# St_Olavs_Alarm_2.net
KiCad netlist of a schematic drawn in Altium Designer
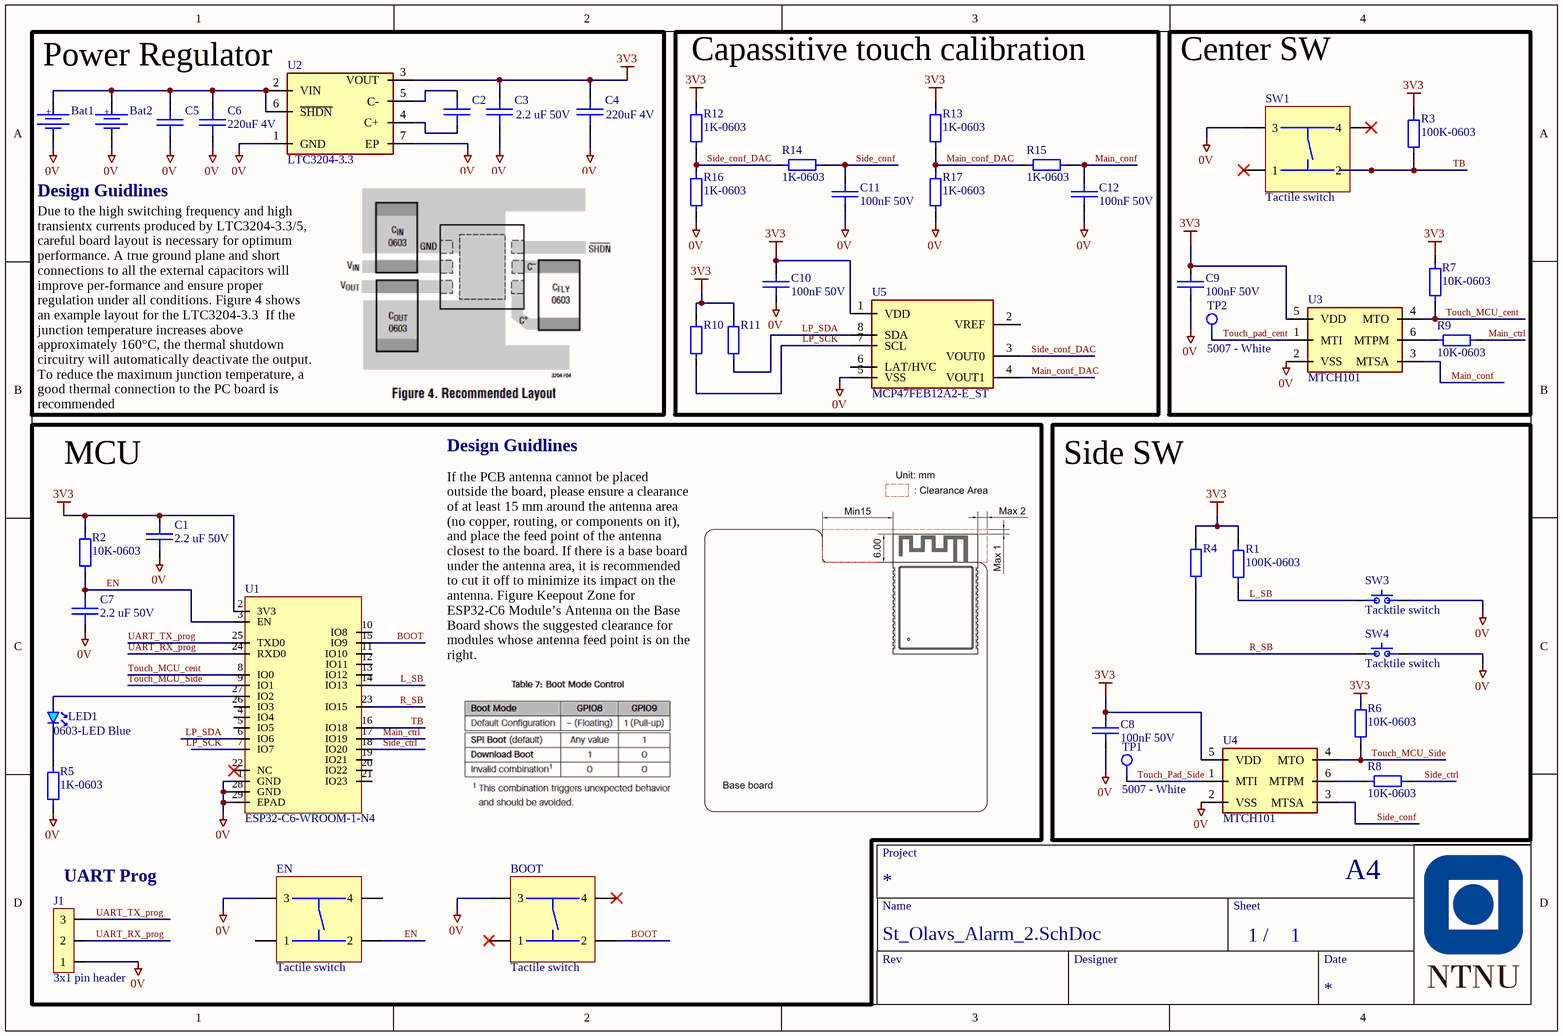
[diagram p0: St_Olavs_Alarm_2.SchDoc]

(export (version "E")
  (design (tool "Eeschema 10.0.6"))
  (components
    (comp (ref "Bat1")
      (value "Bat Holder L-KLS5-CR2032-23-B1")
      (footprint "St_Olavs_alarm:L-KLS5-CR2032-23-B1")
      (description "Bat Holder CR2032 SMD")
      (fields
        (field (name "MANUFACTURER") "KLS Electronic")
        (field (name "MANUFACTURER PART NUMBER") "L-KLS5-CR2032-23-B1")
        (field (name "AUTHOR") "rsk")
      )
      (libsource (lib "St_Olavs_alarm") (part "CMP-023-000003.0.1"))
    )
    (comp (ref "Bat2")
      (value "Bat Holder L-KLS5-CR2032-23-B1")
      (footprint "St_Olavs_alarm:L-KLS5-CR2032-23-B1")
      (description "Bat Holder CR2032 SMD")
      (fields
        (field (name "MANUFACTURER") "KLS Electronic")
        (field (name "MANUFACTURER PART NUMBER") "L-KLS5-CR2032-23-B1")
        (field (name "AUTHOR") "rsk")
      )
      (libsource (lib "St_Olavs_alarm") (part "CMP-023-000003.0.1"))
    )
    (comp (ref "BOOT")
      (value "Tactile switch")
      (footprint "St_Olavs_alarm:TE connectivity part no. 2-1437565-8")
      (description "Tactile switch SMD Mount")
      (libsource (lib "St_Olavs_alarm") (part "Tactile switch SMD"))
    )
    (comp (ref "C1")
      (value "2.2 uF 50V")
      (footprint "St_Olavs_alarm:0603 Capacitor")
      (description "2.2uF 10V 0603")
      (libsource (lib "St_Olavs_alarm") (part "CAP 2.2uF"))
    )
    (comp (ref "C2")
      (value "2.2 uF 50V")
      (footprint "St_Olavs_alarm:0603 Capacitor")
      (description "2.2uF 10V 0603")
      (libsource (lib "St_Olavs_alarm") (part "CAP 2.2uF"))
    )
    (comp (ref "C3")
      (value "2.2 uF 50V")
      (footprint "St_Olavs_alarm:0603 Capacitor")
      (description "2.2uF 10V 0603")
      (libsource (lib "St_Olavs_alarm") (part "CAP 2.2uF"))
    )
    (comp (ref "C4")
      (value "220uF 4V")
      (footprint "St_Olavs_alarm:1206 CAPC3216X190N")
      (description "220uF 4V 1206")
      (libsource (lib "St_Olavs_alarm") (part "CAP 220uF"))
    )
    (comp (ref "C5")
      (value "220uF 4V")
      (footprint "St_Olavs_alarm:1206 CAPC3216X190N")
      (description "220uF 4V 1206")
      (libsource (lib "St_Olavs_alarm") (part "CAP 220uF"))
    )
    (comp (ref "C6")
      (value "220uF 4V")
      (footprint "St_Olavs_alarm:1206 CAPC3216X190N")
      (description "220uF 4V 1206")
      (libsource (lib "St_Olavs_alarm") (part "CAP 220uF"))
    )
    (comp (ref "C7")
      (value "2.2 uF 50V")
      (footprint "St_Olavs_alarm:0603 Capacitor")
      (description "2.2uF 10V 0603")
      (libsource (lib "St_Olavs_alarm") (part "CAP 2.2uF"))
    )
    (comp (ref "C8")
      (value "100nF 50V")
      (footprint "St_Olavs_alarm:0603 Capacitor")
      (description "100nF 50V 0603")
      (libsource (lib "St_Olavs_alarm") (part "CAP 100nF"))
    )
    (comp (ref "C9")
      (value "100nF 50V")
      (footprint "St_Olavs_alarm:0603 Capacitor")
      (description "100nF 50V 0603")
      (libsource (lib "St_Olavs_alarm") (part "CAP 100nF"))
    )
    (comp (ref "C10")
      (value "100nF 50V")
      (footprint "St_Olavs_alarm:0603 Capacitor")
      (description "100nF 50V 0603")
      (libsource (lib "St_Olavs_alarm") (part "CAP 100nF"))
    )
    (comp (ref "C11")
      (value "100nF 50V")
      (footprint "St_Olavs_alarm:0603 Capacitor")
      (description "100nF 50V 0603")
      (libsource (lib "St_Olavs_alarm") (part "CAP 100nF"))
    )
    (comp (ref "C12")
      (value "100nF 50V")
      (footprint "St_Olavs_alarm:0603 Capacitor")
      (description "100nF 50V 0603")
      (libsource (lib "St_Olavs_alarm") (part "CAP 100nF"))
    )
    (comp (ref "EN")
      (value "Tactile switch")
      (footprint "St_Olavs_alarm:TE connectivity part no. 2-1437565-8")
      (description "Tactile switch SMD Mount")
      (libsource (lib "St_Olavs_alarm") (part "Tactile switch SMD"))
    )
    (comp (ref "J1")
      (value "3x1 pin header")
      (footprint "St_Olavs_alarm:Pin Header 1x3 TH Pitch 2.54mm")
      (description "2.54mm pitch")
      (libsource (lib "St_Olavs_alarm") (part "CMP-001-A02-7"))
    )
    (comp (ref "LED1")
      (value "0603-LED Blue")
      (footprint "St_Olavs_alarm:0603-Diode LED, Blue")
      (libsource (lib "St_Olavs_alarm") (part "0603-LED Blue"))
    )
    (comp (ref "R1")
      (value "100K-0603")
      (footprint "St_Olavs_alarm:0603 RESISTOR")
      (description "Res 100K Ohm Thick Film 0603 1% 1/10W ±100ppm/°C Molded SMD SMD Paper T/R")
      (libsource (lib "St_Olavs_alarm") (part "CMP-009-00186-5_1"))
    )
    (comp (ref "R2")
      (value "10K-0603")
      (footprint "St_Olavs_alarm:0603 RESISTOR")
      (description "Res 10K Ohm Thick Film 0603 1% 1/10W ±100ppm/°C Molded SMD SMD Paper T/R")
      (libsource (lib "St_Olavs_alarm") (part "CMP-009-00186-5"))
    )
    (comp (ref "R3")
      (value "100K-0603")
      (footprint "St_Olavs_alarm:0603 RESISTOR")
      (description "Res 100K Ohm Thick Film 0603 1% 1/10W ±100ppm/°C Molded SMD SMD Paper T/R")
      (libsource (lib "St_Olavs_alarm") (part "CMP-009-00186-5_1"))
    )
    (comp (ref "R4")
      (value "100K-0603")
      (footprint "St_Olavs_alarm:0603 RESISTOR")
      (description "Res 100K Ohm Thick Film 0603 1% 1/10W ±100ppm/°C Molded SMD SMD Paper T/R")
      (libsource (lib "St_Olavs_alarm") (part "CMP-009-00186-5_1"))
    )
    (comp (ref "R5")
      (value "1K-0603")
      (footprint "St_Olavs_alarm:0603 RESISTOR")
      (description "Res 1K Ohm Thick Film 0603 1% 1/10W ±100ppm/°C Molded SMD SMD Paper T/R")
      (libsource (lib "St_Olavs_alarm") (part "CMP-009-00186-5_1_1"))
    )
    (comp (ref "R6")
      (value "10K-0603")
      (footprint "St_Olavs_alarm:0603 RESISTOR")
      (description "Res 10K Ohm Thick Film 0603 1% 1/10W ±100ppm/°C Molded SMD SMD Paper T/R")
      (libsource (lib "St_Olavs_alarm") (part "CMP-009-00186-5"))
    )
    (comp (ref "R7")
      (value "10K-0603")
      (footprint "St_Olavs_alarm:0603 RESISTOR")
      (description "Res 10K Ohm Thick Film 0603 1% 1/10W ±100ppm/°C Molded SMD SMD Paper T/R")
      (libsource (lib "St_Olavs_alarm") (part "CMP-009-00186-5"))
    )
    (comp (ref "R8")
      (value "10K-0603")
      (footprint "St_Olavs_alarm:0603 RESISTOR")
      (description "Res 10K Ohm Thick Film 0603 1% 1/10W ±100ppm/°C Molded SMD SMD Paper T/R")
      (libsource (lib "St_Olavs_alarm") (part "CMP-009-00186-5"))
    )
    (comp (ref "R9")
      (value "10K-0603")
      (footprint "St_Olavs_alarm:0603 RESISTOR")
      (description "Res 10K Ohm Thick Film 0603 1% 1/10W ±100ppm/°C Molded SMD SMD Paper T/R")
      (libsource (lib "St_Olavs_alarm") (part "CMP-009-00186-5"))
    )
    (comp (ref "R10")
      (value "10K-0603")
      (footprint "St_Olavs_alarm:0603 RESISTOR")
      (description "Res 10K Ohm Thick Film 0603 1% 1/10W ±100ppm/°C Molded SMD SMD Paper T/R")
      (libsource (lib "St_Olavs_alarm") (part "CMP-009-00186-5"))
    )
    (comp (ref "R11")
      (value "10K-0603")
      (footprint "St_Olavs_alarm:0603 RESISTOR")
      (description "Res 10K Ohm Thick Film 0603 1% 1/10W ±100ppm/°C Molded SMD SMD Paper T/R")
      (libsource (lib "St_Olavs_alarm") (part "CMP-009-00186-5"))
    )
    (comp (ref "R12")
      (value "1K-0603")
      (footprint "St_Olavs_alarm:0603 RESISTOR")
      (description "Res 1K Ohm Thick Film 0603 1% 1/10W ±100ppm/°C Molded SMD SMD Paper T/R")
      (libsource (lib "St_Olavs_alarm") (part "CMP-009-00186-5_1_1"))
    )
    (comp (ref "R13")
      (value "1K-0603")
      (footprint "St_Olavs_alarm:0603 RESISTOR")
      (description "Res 1K Ohm Thick Film 0603 1% 1/10W ±100ppm/°C Molded SMD SMD Paper T/R")
      (libsource (lib "St_Olavs_alarm") (part "CMP-009-00186-5_1_1"))
    )
    (comp (ref "R14")
      (value "1K-0603")
      (footprint "St_Olavs_alarm:0603 RESISTOR")
      (description "Res 1K Ohm Thick Film 0603 1% 1/10W ±100ppm/°C Molded SMD SMD Paper T/R")
      (libsource (lib "St_Olavs_alarm") (part "CMP-009-00186-5_1_1"))
    )
    (comp (ref "R15")
      (value "1K-0603")
      (footprint "St_Olavs_alarm:0603 RESISTOR")
      (description "Res 1K Ohm Thick Film 0603 1% 1/10W ±100ppm/°C Molded SMD SMD Paper T/R")
      (libsource (lib "St_Olavs_alarm") (part "CMP-009-00186-5_1_1"))
    )
    (comp (ref "R16")
      (value "1K-0603")
      (footprint "St_Olavs_alarm:0603 RESISTOR")
      (description "Res 1K Ohm Thick Film 0603 1% 1/10W ±100ppm/°C Molded SMD SMD Paper T/R")
      (libsource (lib "St_Olavs_alarm") (part "CMP-009-00186-5_1_1"))
    )
    (comp (ref "R17")
      (value "1K-0603")
      (footprint "St_Olavs_alarm:0603 RESISTOR")
      (description "Res 1K Ohm Thick Film 0603 1% 1/10W ±100ppm/°C Molded SMD SMD Paper T/R")
      (libsource (lib "St_Olavs_alarm") (part "CMP-009-00186-5_1_1"))
    )
    (comp (ref "SW1")
      (value "Tactile switch")
      (footprint "St_Olavs_alarm:430182080816")
      (description "Tactile switch SMD Longer Neck")
      (libsource (lib "St_Olavs_alarm") (part "Tactile switch Big"))
    )
    (comp (ref "SW3")
      (value "Tacktile switch")
      (footprint "St_Olavs_alarm:KSS241GLFS")
      (description "KSS241GLFS")
      (libsource (lib "St_Olavs_alarm") (part "KSS241GLFS"))
    )
    (comp (ref "SW4")
      (value "Tacktile switch")
      (footprint "St_Olavs_alarm:KSS241GLFS")
      (description "KSS241GLFS")
      (libsource (lib "St_Olavs_alarm") (part "KSS241GLFS"))
    )
    (comp (ref "TP1")
      (value "5007 - White")
      (footprint "St_Olavs_alarm:5006-Footprint-1")
      (description "KEYSTONE - 5007 - TEST POINT, THT, WHITE")
      (libsource (lib "St_Olavs_alarm") (part "CMP-00049-A.2"))
    )
    (comp (ref "TP2")
      (value "5007 - White")
      (footprint "St_Olavs_alarm:5006-Footprint-1")
      (description "KEYSTONE - 5007 - TEST POINT, THT, WHITE")
      (libsource (lib "St_Olavs_alarm") (part "CMP-00049-A.2"))
    )
    (comp (ref "U1")
      (value "ESP32-C6-WROOM-1-N4")
      (footprint "St_Olavs_alarm:ESP32-C6-WROOM-1-N4-Footprint-1")
      (libsource (lib "St_Olavs_alarm") (part "CMP-020-00028-2"))
    )
    (comp (ref "U2")
      (value "LTC3204-3.3")
      (footprint "St_Olavs_alarm:LTC3204")
      (libsource (lib "St_Olavs_alarm") (part "LTC3204-3.3"))
    )
    (comp (ref "U3")
      (value "MTCH101")
      (footprint "St_Olavs_alarm:SOT95P270X145-6N")
      (description "Capasitive touch sensor")
      (fields
        (field (name "MANUFACTURER_PART_NUMBER") "MTCH101-I/OT")
        (field (name "MOUSER PART NUMBER") "579-MTCH101-I/OT")
      )
      (libsource (lib "St_Olavs_alarm") (part "MTCH101-I_OT"))
    )
    (comp (ref "U4")
      (value "MTCH101")
      (footprint "St_Olavs_alarm:SOT95P270X145-6N")
      (description "Capasitive touch sensor")
      (fields
        (field (name "MANUFACTURER_PART_NUMBER") "MTCH101-I/OT")
        (field (name "MOUSER PART NUMBER") "579-MTCH101-I/OT")
      )
      (libsource (lib "St_Olavs_alarm") (part "MTCH101-I_OT"))
    )
    (comp (ref "U5")
      (value "MCP47FEB12A2-E_ST")
      (footprint "St_Olavs_alarm:SOP65P640X120-8N")
      (description "Integrated Circuit")
      (fields
        (field (name "MANUFACTURER_PART_NUMBER") "MCP47FEB12A2-E/ST")
        (field (name "MOUSER PART NUMBER") "579-MCP47FEB12A2EST")
      )
      (libsource (lib "St_Olavs_alarm") (part "MCP47FEB12A2-E_ST"))
    )
  )
  (nets
    (net (code "1") (name "/BOOT") (class "Default")
      (node (ref "BOOT") (pin "2") (pinfunction "2_2") (pintype "passive"))
      (node (ref "U1") (pin "15") (pinfunction "IO9_15") (pintype "passive"))
    )
    (net (code "2") (name "/EN") (class "Default")
      (node (ref "C7") (pin "2") (pinfunction "2_2") (pintype "passive"))
      (node (ref "EN") (pin "2") (pinfunction "2_2") (pintype "passive"))
      (node (ref "R2") (pin "1") (pinfunction "1_1") (pintype "passive"))
      (node (ref "U1") (pin "3") (pinfunction "EN_3") (pintype "passive"))
    )
    (net (code "3") (name "/LP_SCK") (class "Default")
      (node (ref "R10") (pin "1") (pinfunction "1_1") (pintype "passive"))
      (node (ref "U1") (pin "7") (pinfunction "IO7_7") (pintype "passive"))
      (node (ref "U5") (pin "7") (pinfunction "SCL_7") (pintype "passive"))
    )
    (net (code "4") (name "/LP_SDA") (class "Default")
      (node (ref "R11") (pin "1") (pinfunction "1_1") (pintype "passive"))
      (node (ref "U1") (pin "6") (pinfunction "IO6_6") (pintype "passive"))
      (node (ref "U5") (pin "8") (pinfunction "SDA_8") (pintype "passive"))
    )
    (net (code "5") (name "/L_SB") (class "Default")
      (node (ref "R1") (pin "1") (pinfunction "1_1") (pintype "passive"))
      (node (ref "SW3") (pin "1") (pinfunction "1_1") (pintype "passive"))
      (node (ref "U1") (pin "14") (pinfunction "IO13_14") (pintype "passive"))
    )
    (net (code "6") (name "/Main_conf") (class "Default")
      (node (ref "C12") (pin "1") (pinfunction "1_1") (pintype "passive"))
      (node (ref "R15") (pin "1") (pinfunction "1_1") (pintype "passive"))
      (node (ref "U3") (pin "3") (pinfunction "MTSA_3") (pintype "passive"))
    )
    (net (code "7") (name "/Main_conf_DAC") (class "Default")
      (node (ref "R13") (pin "2") (pinfunction "1_2") (pintype "passive"))
      (node (ref "R15") (pin "2") (pinfunction "1_2") (pintype "passive"))
      (node (ref "R17") (pin "1") (pinfunction "1_1") (pintype "passive"))
      (node (ref "U5") (pin "4") (pinfunction "VOUT1_4") (pintype "passive"))
    )
    (net (code "8") (name "/Main_ctrl") (class "Default")
      (node (ref "R9") (pin "1") (pinfunction "1_1") (pintype "passive"))
      (node (ref "U1") (pin "17") (pinfunction "IO19_17") (pintype "passive"))
    )
    (net (code "9") (name "/R_SB") (class "Default")
      (node (ref "R4") (pin "1") (pinfunction "1_1") (pintype "passive"))
      (node (ref "SW4") (pin "1") (pinfunction "1_1") (pintype "passive"))
      (node (ref "U1") (pin "23") (pinfunction "IO15_23") (pintype "passive"))
    )
    (net (code "10") (name "/Side_conf") (class "Default")
      (node (ref "C11") (pin "1") (pinfunction "1_1") (pintype "passive"))
      (node (ref "R14") (pin "2") (pinfunction "1_2") (pintype "passive"))
      (node (ref "U4") (pin "3") (pinfunction "MTSA_3") (pintype "passive"))
    )
    (net (code "11") (name "/Side_conf_DAC") (class "Default")
      (node (ref "R12") (pin "1") (pinfunction "1_1") (pintype "passive"))
      (node (ref "R14") (pin "1") (pinfunction "1_1") (pintype "passive"))
      (node (ref "R16") (pin "2") (pinfunction "1_2") (pintype "passive"))
      (node (ref "U5") (pin "3") (pinfunction "VOUT0_3") (pintype "passive"))
    )
    (net (code "12") (name "/Side_ctrl") (class "Default")
      (node (ref "R8") (pin "2") (pinfunction "1_2") (pintype "passive"))
      (node (ref "U1") (pin "18") (pinfunction "IO20_18") (pintype "passive"))
    )
    (net (code "13") (name "/TB") (class "Default")
      (node (ref "R3") (pin "1") (pinfunction "1_1") (pintype "passive"))
      (node (ref "SW1") (pin "2") (pinfunction "2_2") (pintype "passive"))
      (node (ref "U1") (pin "16") (pinfunction "IO18_16") (pintype "passive"))
    )
    (net (code "14") (name "/Touch_MCU_Side") (class "Default")
      (node (ref "R6") (pin "1") (pinfunction "1_1") (pintype "passive"))
      (node (ref "U1") (pin "9") (pinfunction "IO1_9") (pintype "passive"))
      (node (ref "U4") (pin "4") (pinfunction "MTO_4") (pintype "passive"))
    )
    (net (code "15") (name "/Touch_MCU_cent") (class "Default")
      (node (ref "R7") (pin "1") (pinfunction "1_1") (pintype "passive"))
      (node (ref "U1") (pin "8") (pinfunction "IO0_8") (pintype "passive"))
      (node (ref "U3") (pin "4") (pinfunction "MTO_4") (pintype "passive"))
    )
    (net (code "16") (name "/Touch_Pad_Side") (class "Default")
      (node (ref "TP1") (pin "1") (pinfunction "1_1") (pintype "passive"))
      (node (ref "U4") (pin "1") (pinfunction "MTI_1") (pintype "passive"))
    )
    (net (code "17") (name "/Touch_pad_cent") (class "Default")
      (node (ref "TP2") (pin "1") (pinfunction "1_1") (pintype "passive"))
      (node (ref "U3") (pin "1") (pinfunction "MTI_1") (pintype "passive"))
    )
    (net (code "18") (name "/UART_RX_prog") (class "Default")
      (node (ref "J1") (pin "2") (pinfunction "2_2") (pintype "passive"))
      (node (ref "U1") (pin "24") (pinfunction "RXD0_24") (pintype "passive"))
    )
    (net (code "19") (name "/UART_TX_prog") (class "Default")
      (node (ref "J1") (pin "3") (pinfunction "3_3") (pintype "passive"))
      (node (ref "U1") (pin "25") (pinfunction "TXD0_25") (pintype "passive"))
    )
    (net (code "20") (name "0V") (class "Default")
      (node (ref "BOOT") (pin "3") (pinfunction "3_3") (pintype "passive"))
      (node (ref "Bat1") (pin "2") (pintype "passive"))
      (node (ref "Bat2") (pin "2") (pintype "passive"))
      (node (ref "C1") (pin "1") (pinfunction "1_1") (pintype "passive"))
      (node (ref "C10") (pin "2") (pinfunction "2_2") (pintype "passive"))
      (node (ref "C11") (pin "2") (pinfunction "2_2") (pintype "passive"))
      (node (ref "C12") (pin "2") (pinfunction "2_2") (pintype "passive"))
      (node (ref "C3") (pin "1") (pinfunction "1_1") (pintype "passive"))
      (node (ref "C4") (pin "2") (pinfunction "2_2") (pintype "passive"))
      (node (ref "C5") (pin "2") (pinfunction "2_2") (pintype "passive"))
      (node (ref "C6") (pin "2") (pinfunction "2_2") (pintype "passive"))
      (node (ref "C7") (pin "1") (pinfunction "1_1") (pintype "passive"))
      (node (ref "C8") (pin "2") (pinfunction "2_2") (pintype "passive"))
      (node (ref "C9") (pin "2") (pinfunction "2_2") (pintype "passive"))
      (node (ref "EN") (pin "3") (pinfunction "3_3") (pintype "passive"))
      (node (ref "J1") (pin "1") (pinfunction "1_1") (pintype "passive"))
      (node (ref "R16") (pin "1") (pinfunction "1_1") (pintype "passive"))
      (node (ref "R17") (pin "2") (pinfunction "1_2") (pintype "passive"))
      (node (ref "R5") (pin "1") (pinfunction "1_1") (pintype "passive"))
      (node (ref "SW1") (pin "3") (pinfunction "3_3") (pintype "passive"))
      (node (ref "SW3") (pin "2") (pinfunction "2_2") (pintype "passive"))
      (node (ref "SW4") (pin "2") (pinfunction "2_2") (pintype "passive"))
      (node (ref "U1") (pin "1") (pinfunction "GND_1") (pintype "passive"))
      (node (ref "U1") (pin "28") (pinfunction "GND_28") (pintype "power_in"))
      (node (ref "U1") (pin "29") (pinfunction "EPAD_29") (pintype "power_in"))
      (node (ref "U2") (pin "1") (pinfunction "GND_1") (pintype "passive"))
      (node (ref "U2") (pin "7") (pinfunction "EP_7") (pintype "passive"))
      (node (ref "U3") (pin "2") (pinfunction "VSS_2") (pintype "passive"))
      (node (ref "U4") (pin "2") (pinfunction "VSS_2") (pintype "passive"))
      (node (ref "U5") (pin "5") (pinfunction "VSS_5") (pintype "passive"))
    )
    (net (code "21") (name "3V3") (class "Default")
      (node (ref "C1") (pin "2") (pinfunction "2_2") (pintype "passive"))
      (node (ref "C10") (pin "1") (pinfunction "1_1") (pintype "passive"))
      (node (ref "C3") (pin "2") (pinfunction "2_2") (pintype "passive"))
      (node (ref "C4") (pin "1") (pinfunction "1_1") (pintype "passive"))
      (node (ref "C8") (pin "1") (pinfunction "1_1") (pintype "passive"))
      (node (ref "C9") (pin "1") (pinfunction "1_1") (pintype "passive"))
      (node (ref "R1") (pin "2") (pinfunction "1_2") (pintype "passive"))
      (node (ref "R10") (pin "2") (pinfunction "1_2") (pintype "passive"))
      (node (ref "R11") (pin "2") (pinfunction "1_2") (pintype "passive"))
      (node (ref "R12") (pin "2") (pinfunction "1_2") (pintype "passive"))
      (node (ref "R13") (pin "1") (pinfunction "1_1") (pintype "passive"))
      (node (ref "R2") (pin "2") (pinfunction "1_2") (pintype "passive"))
      (node (ref "R3") (pin "2") (pinfunction "1_2") (pintype "passive"))
      (node (ref "R4") (pin "2") (pinfunction "1_2") (pintype "passive"))
      (node (ref "R6") (pin "2") (pinfunction "1_2") (pintype "passive"))
      (node (ref "R7") (pin "2") (pinfunction "1_2") (pintype "passive"))
      (node (ref "U1") (pin "2") (pinfunction "3V3_2") (pintype "passive"))
      (node (ref "U2") (pin "3") (pinfunction "VOUT_3") (pintype "passive"))
      (node (ref "U3") (pin "5") (pinfunction "VDD_5") (pintype "passive"))
      (node (ref "U4") (pin "5") (pinfunction "VDD_5") (pintype "passive"))
      (node (ref "U5") (pin "1") (pinfunction "VDD_1") (pintype "passive"))
    )
    (net (code "22") (name "Net-(LED1-A)") (class "Default")
      (node (ref "LED1") (pin "1") (pinfunction "A_1") (pintype "passive"))
      (node (ref "U1") (pin "27") (pinfunction "IO2_27") (pintype "passive"))
    )
    (net (code "23") (name "Net-(LED1-K)") (class "Default")
      (node (ref "LED1") (pin "2") (pinfunction "K_2") (pintype "passive"))
      (node (ref "R5") (pin "2") (pinfunction "1_2") (pintype "passive"))
    )
    (net (code "24") (name "Net-(U2-C+)") (class "Default")
      (node (ref "C2") (pin "1") (pinfunction "1_1") (pintype "passive"))
      (node (ref "U2") (pin "4") (pinfunction "C+_4") (pintype "passive"))
    )
    (net (code "25") (name "Net-(U2-C-)") (class "Default")
      (node (ref "C2") (pin "2") (pinfunction "2_2") (pintype "passive"))
      (node (ref "U2") (pin "5") (pinfunction "C-_5") (pintype "passive"))
    )
    (net (code "26") (name "Net-(U2-VIN)") (class "Default")
      (node (ref "Bat1") (pin "1") (pintype "passive"))
      (node (ref "Bat2") (pin "1") (pintype "passive"))
      (node (ref "C5") (pin "1") (pinfunction "1_1") (pintype "passive"))
      (node (ref "C6") (pin "1") (pinfunction "1_1") (pintype "passive"))
      (node (ref "U2") (pin "2") (pinfunction "VIN_2") (pintype "passive"))
      (node (ref "U2") (pin "6") (pinfunction "~{SHDN}_6") (pintype "passive"))
    )
    (net (code "27") (name "Net-(U3-MTPM)") (class "Default")
      (node (ref "R9") (pin "2") (pinfunction "1_2") (pintype "passive"))
      (node (ref "U3") (pin "6") (pinfunction "MTPM_6") (pintype "passive"))
    )
    (net (code "28") (name "Net-(U4-MTPM)") (class "Default")
      (node (ref "R8") (pin "1") (pinfunction "1_1") (pintype "passive"))
      (node (ref "U4") (pin "6") (pinfunction "MTPM_6") (pintype "passive"))
    )
    (net (code "29") (name "unconnected-(BOOT-Pad1)") (class "Default")
      (node (ref "BOOT") (pin "1") (pinfunction "1_1") (pintype "passive+no_connect"))
    )
    (net (code "30") (name "unconnected-(BOOT-Pad4)") (class "Default")
      (node (ref "BOOT") (pin "4") (pinfunction "4_4") (pintype "passive+no_connect"))
    )
    (net (code "31") (name "unconnected-(EN-Pad1)") (class "Default")
      (node (ref "EN") (pin "1") (pinfunction "1_1") (pintype "passive"))
    )
    (net (code "32") (name "unconnected-(EN-Pad4)") (class "Default")
      (node (ref "EN") (pin "4") (pinfunction "4_4") (pintype "passive"))
    )
    (net (code "33") (name "unconnected-(SW1-Pad1)") (class "Default")
      (node (ref "SW1") (pin "1") (pinfunction "1_1") (pintype "passive+no_connect"))
    )
    (net (code "34") (name "unconnected-(SW1-Pad4)") (class "Default")
      (node (ref "SW1") (pin "4") (pinfunction "4_4") (pintype "passive+no_connect"))
    )
    (net (code "35") (name "unconnected-(U1-IO3-Pad26)") (class "Default")
      (node (ref "U1") (pin "26") (pinfunction "IO3_26") (pintype "passive"))
    )
    (net (code "36") (name "unconnected-(U1-IO4-Pad4)") (class "Default")
      (node (ref "U1") (pin "4") (pinfunction "IO4_4") (pintype "passive"))
    )
    (net (code "37") (name "unconnected-(U1-IO5-Pad5)") (class "Default")
      (node (ref "U1") (pin "5") (pinfunction "IO5_5") (pintype "passive"))
    )
    (net (code "38") (name "unconnected-(U1-IO8-Pad10)") (class "Default")
      (node (ref "U1") (pin "10") (pinfunction "IO8_10") (pintype "passive"))
    )
    (net (code "39") (name "unconnected-(U1-IO10-Pad11)") (class "Default")
      (node (ref "U1") (pin "11") (pinfunction "IO10_11") (pintype "passive"))
    )
    (net (code "40") (name "unconnected-(U1-IO11-Pad12)") (class "Default")
      (node (ref "U1") (pin "12") (pinfunction "IO11_12") (pintype "passive"))
    )
    (net (code "41") (name "unconnected-(U1-IO12-Pad13)") (class "Default")
      (node (ref "U1") (pin "13") (pinfunction "IO12_13") (pintype "passive"))
    )
    (net (code "42") (name "unconnected-(U1-IO21-Pad19)") (class "Default")
      (node (ref "U1") (pin "19") (pinfunction "IO21_19") (pintype "passive"))
    )
    (net (code "43") (name "unconnected-(U1-IO22-Pad20)") (class "Default")
      (node (ref "U1") (pin "20") (pinfunction "IO22_20") (pintype "passive"))
    )
    (net (code "44") (name "unconnected-(U1-IO23-Pad21)") (class "Default")
      (node (ref "U1") (pin "21") (pinfunction "IO23_21") (pintype "passive"))
    )
    (net (code "45") (name "unconnected-(U1-NC-Pad22)") (class "Default")
      (node (ref "U1") (pin "22") (pinfunction "NC_22") (pintype "passive+no_connect"))
    )
    (net (code "46") (name "unconnected-(U5-LAT{slash}HVC-Pad6)") (class "Default")
      (node (ref "U5") (pin "6") (pinfunction "LAT/HVC_6") (pintype "passive"))
    )
    (net (code "47") (name "unconnected-(U5-VREF-Pad2)") (class "Default")
      (node (ref "U5") (pin "2") (pinfunction "VREF_2") (pintype "passive"))
    )
  )
)
